# mcu.net
KiCad netlist of a schematic drawn in Altium Designer
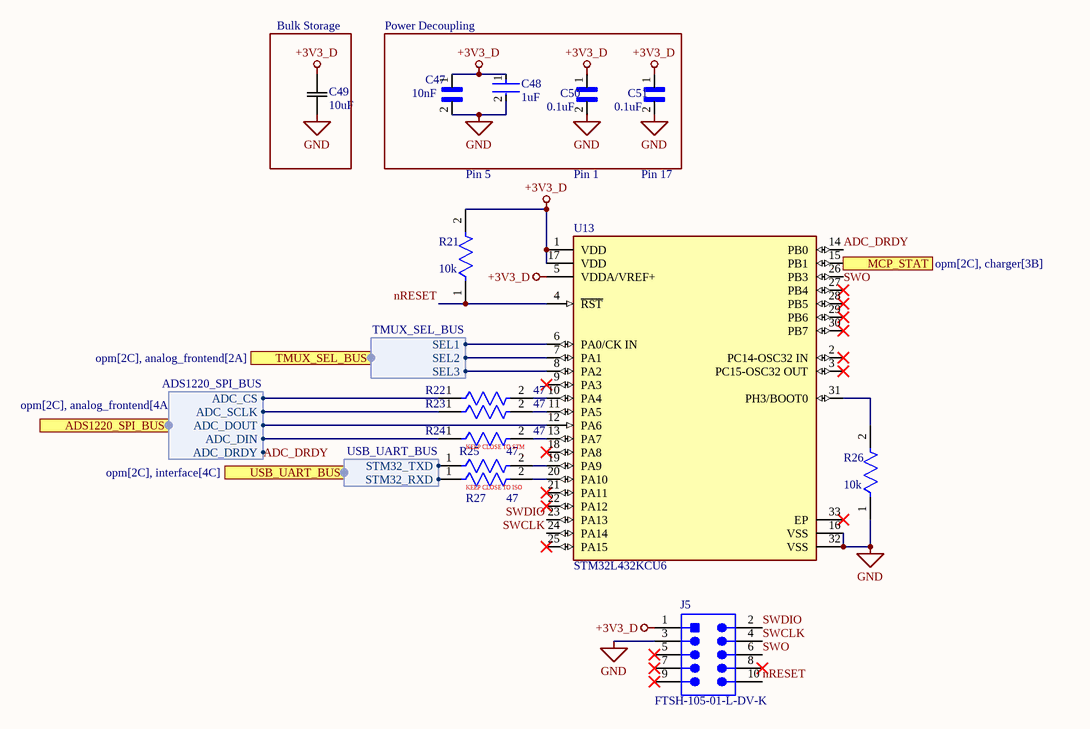
[diagram p0: mcu.SchDoc]

(export (version "E")
  (design (tool "Eeschema 10.0.6"))
  (components
    (comp (ref "C47")
      (value "10nF")
      (footprint "CC0603JRX7R8BB104")
      (description "25V 10nF X7R ±5% 0603 Multilayer Ceramic Capacitors MLCC - SMD/SMT ROHS")
      (fields
        (field (name "MANUFACTURER") "Yageo Group")
        (field (name "MANUFACTURER PART NUMBER") "CC0603JRX7R8BB103")
      )
      (libsource (lib "opm_lib") (part "CC0603JRX7R8BB103"))
    )
    (comp (ref "C48")
      (value "1uF")
      (footprint "CC0805KKX7R7BB106")
      (description "16V 1uF X7R ±10% 0805 Multilayer Ceramic Capacitors MLCC - SMD/SMT ROHS")
      (fields
        (field (name "MANUFACTURER") "Yageo Group")
        (field (name "MANUFACTURER PART NUMBER") "CC0805KKX7R7BB105")
      )
      (libsource (lib "opm_lib") (part "CC0805KKX7R7BB105"))
    )
    (comp (ref "C49")
      (value "10uF")
      (footprint "CC0805KKX7R7BB106")
      (description "16V 10uF X7R ±10% 0805 Multilayer Ceramic Capacitors MLCC - SMD/SMT ROHS")
      (fields
        (field (name "MANUFACTURER") "Yageo Group")
        (field (name "MANUFACTURER PART NUMBER") "CC0805KKX7R7BB106")
      )
      (libsource (lib "opm_lib") (part "CC0805KKX7R7BB106"))
    )
    (comp (ref "C50")
      (value "0.1uF")
      (footprint "CC0603JRX7R8BB104")
      (description "25V 100nF X7R ±5% 0603 Multilayer Ceramic Capacitors MLCC - SMD/SMT ROHS")
      (fields
        (field (name "MANUFACTURER") "Yageo Group")
        (field (name "MANUFACTURER PART NUMBER") "CC0603JRX7R8BB104")
      )
      (libsource (lib "opm_lib") (part "CC0603JRX7R8BB104"))
    )
    (comp (ref "C51")
      (value "0.1uF")
      (footprint "CC0603JRX7R8BB104")
      (description "25V 100nF X7R ±5% 0603 Multilayer Ceramic Capacitors MLCC - SMD/SMT ROHS")
      (fields
        (field (name "MANUFACTURER") "Yageo Group")
        (field (name "MANUFACTURER PART NUMBER") "CC0603JRX7R8BB104")
      )
      (libsource (lib "opm_lib") (part "CC0603JRX7R8BB104"))
    )
    (comp (ref "J5")
      (value "FTSH-105-01-L-DV-K")
      (footprint "SMTC-FTSH-105-01-L-DV-K_V")
      (description "Conn Shrouded Header (2 Sides) HDR 10 POS 1.27mm Solder ST Top Entry SMD TIGER CLAW™ Tube")
      (fields (field (name "MANUFACTURER") "Samtec"))
      (libsource (lib "opm_lib") (part "FTSH-105-01-L-DV-K"))
    )
    (comp (ref "R21")
      (value "10k")
      (footprint "RC0603FR-07")
      (description "100mW Thick Film Resistors 75V ±100ppm/℃ ±1% 10kΩ 0603 Chip Resistor - Surface Mount ROHS")
      (fields
        (field (name "MANUFACTURER") "Yageo Group")
        (field (name "MANUFACTURER PART NUMBER") "RC0603FR-0710KL")
      )
      (libsource (lib "opm_lib") (part "RC0603FR-0710KL"))
    )
    (comp (ref "R22")
      (value "47")
      (footprint "RC0603FR-07")
      (description "100mW Thick Film Resistors 75V ±100ppm/℃ ±1% 47Ω 0603 Chip Resistor - Surface Mount ROHS")
      (fields
        (field (name "MANUFACTURER") "Yageo Group")
        (field (name "MANUFACTURER PART NUMBER") "RC0603FR-0747RL")
      )
      (libsource (lib "opm_lib") (part "RC0603FR-0747RL"))
    )
    (comp (ref "R23")
      (value "47")
      (footprint "RC0603FR-07")
      (description "100mW Thick Film Resistors 75V ±100ppm/℃ ±1% 47Ω 0603 Chip Resistor - Surface Mount ROHS")
      (fields
        (field (name "MANUFACTURER") "Yageo Group")
        (field (name "MANUFACTURER PART NUMBER") "RC0603FR-0747RL")
      )
      (libsource (lib "opm_lib") (part "RC0603FR-0747RL"))
    )
    (comp (ref "R24")
      (value "47")
      (footprint "RC0603FR-07")
      (description "100mW Thick Film Resistors 75V ±100ppm/℃ ±1% 47Ω 0603 Chip Resistor - Surface Mount ROHS")
      (fields
        (field (name "MANUFACTURER") "Yageo Group")
        (field (name "MANUFACTURER PART NUMBER") "RC0603FR-0747RL")
      )
      (libsource (lib "opm_lib") (part "RC0603FR-0747RL"))
    )
    (comp (ref "R25")
      (value "47")
      (footprint "RC0603FR-07")
      (description "100mW Thick Film Resistors 75V ±100ppm/℃ ±1% 47Ω 0603 Chip Resistor - Surface Mount ROHS")
      (fields
        (field (name "MANUFACTURER") "Yageo Group")
        (field (name "MANUFACTURER PART NUMBER") "RC0603FR-0747RL")
      )
      (libsource (lib "opm_lib") (part "RC0603FR-0747RL"))
    )
    (comp (ref "R26")
      (value "10k")
      (footprint "RC0603FR-07")
      (description "100mW Thick Film Resistors 75V ±100ppm/℃ ±1% 10kΩ 0603 Chip Resistor - Surface Mount ROHS")
      (fields
        (field (name "MANUFACTURER") "Yageo Group")
        (field (name "MANUFACTURER PART NUMBER") "RC0603FR-0710KL")
      )
      (libsource (lib "opm_lib") (part "RC0603FR-0710KL"))
    )
    (comp (ref "R27")
      (value "47")
      (footprint "RC0603FR-07")
      (description "100mW Thick Film Resistors 75V ±100ppm/℃ ±1% 47Ω 0603 Chip Resistor - Surface Mount ROHS")
      (fields
        (field (name "MANUFACTURER") "Yageo Group")
        (field (name "MANUFACTURER PART NUMBER") "RC0603FR-0747RL")
      )
      (libsource (lib "opm_lib") (part "RC0603FR-0747RL"))
    )
    (comp (ref "U13")
      (value "STM32L432KCU6")
      (footprint "STM32L432KCU6")
      (description "MCU 32-bit Ultra Low Power STM32L ARM Cortex-M4 RISC 256kB Flash 32-Pin QFN ECOPACK2 Tray")
      (fields (field (name "MANUFACTURER") "STMicroelectronics"))
      (libsource (lib "opm_lib") (part "STM32L432KCU6"))
    )
  )
  (nets
    (net (code "4") (name "+3V3_D") (class "Default")
      (node (ref "C47") (pin "1") (pinfunction "1_1") (pintype "passive"))
      (node (ref "C48") (pin "1") (pinfunction "1_1") (pintype "passive"))
      (node (ref "C49") (pin "1") (pinfunction "1_1") (pintype "passive"))
      (node (ref "C50") (pin "1") (pinfunction "1_1") (pintype "passive"))
      (node (ref "C51") (pin "1") (pinfunction "1_1") (pintype "passive"))
      (node (ref "J5") (pin "1") (pinfunction "1_1") (pintype "passive"))
      (node (ref "R21") (pin "2") (pinfunction "2_2") (pintype "passive"))
      (node (ref "U13") (pin "1") (pinfunction "VDD_1") (pintype "power_in"))
      (node (ref "U13") (pin "17") (pinfunction "VDD_17") (pintype "power_in"))
      (node (ref "U13") (pin "5") (pinfunction "VDDA/VREF+_5") (pintype "power_in"))
    )
    (net (code "5") (name "/ADC_CS") (class "Default")
      (node (ref "R22") (pin "1") (pinfunction "1_1") (pintype "passive"))
    )
    (net (code "6") (name "/ADC_DIN") (class "Default")
      (node (ref "R24") (pin "1") (pinfunction "1_1") (pintype "passive"))
    )
    (net (code "7") (name "/ADC_DOUT") (class "Default")
      (node (ref "U13") (pin "12") (pinfunction "PA6_12") (pintype "input"))
    )
    (net (code "8") (name "/ADC_DRDY") (class "Default")
      (node (ref "U13") (pin "14") (pinfunction "PB0_14") (pintype "bidirectional"))
    )
    (net (code "9") (name "/ADC_SCLK") (class "Default")
      (node (ref "R23") (pin "1") (pinfunction "1_1") (pintype "passive"))
    )
    (net (code "10") (name "/MCP_STAT") (class "Default")
      (node (ref "U13") (pin "15") (pinfunction "PB1_15") (pintype "bidirectional"))
    )
    (net (code "11") (name "/SEL1") (class "Default")
      (node (ref "U13") (pin "6") (pinfunction "PA0/CK_IN_6") (pintype "bidirectional"))
    )
    (net (code "12") (name "/SEL2") (class "Default")
      (node (ref "U13") (pin "7") (pinfunction "PA1_7") (pintype "bidirectional"))
    )
    (net (code "13") (name "/SEL3") (class "Default")
      (node (ref "U13") (pin "8") (pinfunction "PA2_8") (pintype "bidirectional"))
    )
    (net (code "14") (name "/STM32_RXD") (class "Default")
      (node (ref "R27") (pin "1") (pinfunction "1_1") (pintype "passive"))
    )
    (net (code "15") (name "/STM32_TXD") (class "Default")
      (node (ref "R25") (pin "1") (pinfunction "1_1") (pintype "passive"))
    )
    (net (code "16") (name "/SWCLK") (class "Default")
      (node (ref "J5") (pin "4") (pinfunction "4_4") (pintype "passive"))
      (node (ref "U13") (pin "24") (pinfunction "PA14_24") (pintype "bidirectional"))
    )
    (net (code "17") (name "/SWDIO") (class "Default")
      (node (ref "J5") (pin "2") (pinfunction "2_2") (pintype "passive"))
      (node (ref "U13") (pin "23") (pinfunction "PA13_23") (pintype "bidirectional"))
    )
    (net (code "18") (name "/SWO") (class "Default")
      (node (ref "J5") (pin "6") (pinfunction "6_6") (pintype "passive"))
      (node (ref "U13") (pin "26") (pinfunction "PB3_26") (pintype "bidirectional"))
    )
    (net (code "19") (name "/nRESET") (class "Default")
      (node (ref "J5") (pin "10") (pinfunction "10_10") (pintype "passive"))
      (node (ref "R21") (pin "1") (pinfunction "1_1") (pintype "passive"))
      (node (ref "U13") (pin "4") (pinfunction "~{RST}_4") (pintype "input"))
    )
    (net (code "23") (name "GND") (class "Default")
      (node (ref "C47") (pin "2") (pinfunction "2_2") (pintype "passive"))
      (node (ref "C48") (pin "2") (pinfunction "2_2") (pintype "passive"))
      (node (ref "C49") (pin "2") (pinfunction "2_2") (pintype "passive"))
      (node (ref "C50") (pin "2") (pinfunction "2_2") (pintype "passive"))
      (node (ref "C51") (pin "2") (pinfunction "2_2") (pintype "passive"))
      (node (ref "J5") (pin "3") (pinfunction "3_3") (pintype "passive"))
      (node (ref "R26") (pin "1") (pinfunction "1_1") (pintype "passive"))
      (node (ref "U13") (pin "16") (pinfunction "VSS_16") (pintype "power_in"))
      (node (ref "U13") (pin "32") (pinfunction "VSS_32") (pintype "power_in"))
    )
    (net (code "24") (name "Net-(U13-PA4)") (class "Default")
      (node (ref "R22") (pin "2") (pinfunction "2_2") (pintype "passive"))
      (node (ref "U13") (pin "10") (pinfunction "PA4_10") (pintype "bidirectional"))
    )
    (net (code "25") (name "Net-(U13-PA5)") (class "Default")
      (node (ref "R23") (pin "2") (pinfunction "2_2") (pintype "passive"))
      (node (ref "U13") (pin "11") (pinfunction "PA5_11") (pintype "bidirectional"))
    )
    (net (code "26") (name "Net-(U13-PA7)") (class "Default")
      (node (ref "R24") (pin "2") (pinfunction "2_2") (pintype "passive"))
      (node (ref "U13") (pin "13") (pinfunction "PA7_13") (pintype "bidirectional"))
    )
    (net (code "27") (name "Net-(U13-PA9)") (class "Default")
      (node (ref "R25") (pin "2") (pinfunction "2_2") (pintype "passive"))
      (node (ref "U13") (pin "19") (pinfunction "PA9_19") (pintype "bidirectional"))
    )
    (net (code "28") (name "Net-(U13-PA10)") (class "Default")
      (node (ref "R27") (pin "2") (pinfunction "2_2") (pintype "passive"))
      (node (ref "U13") (pin "20") (pinfunction "PA10_20") (pintype "bidirectional"))
    )
    (net (code "29") (name "Net-(U13-PH3{slash}BOOT0)") (class "Default")
      (node (ref "R26") (pin "2") (pinfunction "2_2") (pintype "passive"))
      (node (ref "U13") (pin "31") (pinfunction "PH3/BOOT0_31") (pintype "bidirectional"))
    )
    (net (code "30") (name "unconnected-(J5-Pad5)") (class "Default")
      (node (ref "J5") (pin "5") (pinfunction "5_5") (pintype "passive+no_connect"))
    )
    (net (code "31") (name "unconnected-(J5-Pad7)") (class "Default")
      (node (ref "J5") (pin "7") (pinfunction "7_7") (pintype "passive+no_connect"))
    )
    (net (code "32") (name "unconnected-(J5-Pad8)") (class "Default")
      (node (ref "J5") (pin "8") (pinfunction "8_8") (pintype "passive+no_connect"))
    )
    (net (code "33") (name "unconnected-(J5-Pad9)") (class "Default")
      (node (ref "J5") (pin "9") (pinfunction "9_9") (pintype "passive+no_connect"))
    )
    (net (code "34") (name "unconnected-(U13-EP-Pad33)") (class "Default")
      (node (ref "U13") (pin "33") (pinfunction "EP_33") (pintype "power_in+no_connect"))
    )
    (net (code "35") (name "unconnected-(U13-PA3-Pad9)") (class "Default")
      (node (ref "U13") (pin "9") (pinfunction "PA3_9") (pintype "bidirectional+no_connect"))
    )
    (net (code "36") (name "unconnected-(U13-PA8-Pad18)") (class "Default")
      (node (ref "U13") (pin "18") (pinfunction "PA8_18") (pintype "bidirectional+no_connect"))
    )
    (net (code "37") (name "unconnected-(U13-PA11-Pad21)") (class "Default")
      (node (ref "U13") (pin "21") (pinfunction "PA11_21") (pintype "bidirectional+no_connect"))
    )
    (net (code "38") (name "unconnected-(U13-PA12-Pad22)") (class "Default")
      (node (ref "U13") (pin "22") (pinfunction "PA12_22") (pintype "bidirectional+no_connect"))
    )
    (net (code "39") (name "unconnected-(U13-PA15-Pad25)") (class "Default")
      (node (ref "U13") (pin "25") (pinfunction "PA15_25") (pintype "bidirectional+no_connect"))
    )
    (net (code "40") (name "unconnected-(U13-PB4-Pad27)") (class "Default")
      (node (ref "U13") (pin "27") (pinfunction "PB4_27") (pintype "bidirectional+no_connect"))
    )
    (net (code "41") (name "unconnected-(U13-PB5-Pad28)") (class "Default")
      (node (ref "U13") (pin "28") (pinfunction "PB5_28") (pintype "bidirectional+no_connect"))
    )
    (net (code "42") (name "unconnected-(U13-PB6-Pad29)") (class "Default")
      (node (ref "U13") (pin "29") (pinfunction "PB6_29") (pintype "bidirectional+no_connect"))
    )
    (net (code "43") (name "unconnected-(U13-PB7-Pad30)") (class "Default")
      (node (ref "U13") (pin "30") (pinfunction "PB7_30") (pintype "bidirectional+no_connect"))
    )
    (net (code "44") (name "unconnected-(U13-PC14-OSC32_IN-Pad2)") (class "Default")
      (node (ref "U13") (pin "2") (pinfunction "PC14-OSC32_IN_2") (pintype "bidirectional+no_connect"))
    )
    (net (code "45") (name "unconnected-(U13-PC15-OSC32_OUT-Pad3)") (class "Default")
      (node (ref "U13") (pin "3") (pinfunction "PC15-OSC32_OUT_3") (pintype "bidirectional+no_connect"))
    )
  )
)
